# HoloCubicMCU_211230.net
KiCad netlist of a schematic drawn in Altium Designer
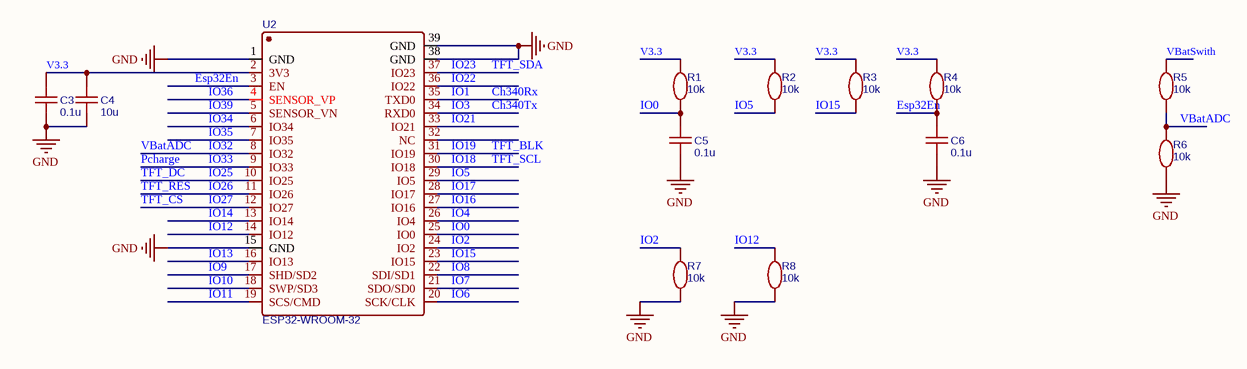
[diagram p0: HoloCubicMCU_211230.SchDoc]

(export (version "E")
  (design (tool "Eeschema 10.0.6"))
  (components
    (comp (ref "C3")
      (value "0.1u")
      (footprint "C0603")
      (fields (field (name "CONTRIBUTOR") "LCEDA_Lib"))
      (libsource (lib "altium-import") (part "root_1_0.1u_"))
    )
    (comp (ref "C4")
      (value "10u")
      (footprint "C0603")
      (fields (field (name "CONTRIBUTOR") "LCEDA_Lib"))
      (libsource (lib "altium-import") (part "root_1_0.1u_"))
    )
    (comp (ref "C5")
      (value "0.1u")
      (footprint "C0603")
      (fields (field (name "CONTRIBUTOR") "LCEDA_Lib"))
      (libsource (lib "altium-import") (part "root_1_0.1u_"))
    )
    (comp (ref "C6")
      (value "0.1u")
      (footprint "C0603")
      (fields (field (name "CONTRIBUTOR") "LCEDA_Lib"))
      (libsource (lib "altium-import") (part "root_1_0.1u_"))
    )
    (comp (ref "R1")
      (value "10k")
      (footprint "R0603")
      (fields (field (name "CONTRIBUTOR") "LCEDA_Lib"))
      (libsource (lib "altium-import") (part "root_1_10k_"))
    )
    (comp (ref "R2")
      (value "10k")
      (footprint "R0603")
      (fields (field (name "CONTRIBUTOR") "LCEDA_Lib"))
      (libsource (lib "altium-import") (part "root_1_10k_"))
    )
    (comp (ref "R3")
      (value "10k")
      (footprint "R0603")
      (fields (field (name "CONTRIBUTOR") "LCEDA_Lib"))
      (libsource (lib "altium-import") (part "root_1_10k_"))
    )
    (comp (ref "R4")
      (value "10k")
      (footprint "R0603")
      (fields (field (name "CONTRIBUTOR") "LCEDA_Lib"))
      (libsource (lib "altium-import") (part "root_1_10k_"))
    )
    (comp (ref "R5")
      (value "10k")
      (footprint "R0603")
      (fields (field (name "CONTRIBUTOR") "LCEDA_Lib"))
      (libsource (lib "altium-import") (part "root_1_10k_"))
    )
    (comp (ref "R6")
      (value "10k")
      (footprint "R0603")
      (fields (field (name "CONTRIBUTOR") "LCEDA_Lib"))
      (libsource (lib "altium-import") (part "root_1_10k_"))
    )
    (comp (ref "R7")
      (value "10k")
      (footprint "R0603")
      (fields (field (name "CONTRIBUTOR") "LCEDA_Lib"))
      (libsource (lib "altium-import") (part "root_1_10k_"))
    )
    (comp (ref "R8")
      (value "10k")
      (footprint "R0603")
      (fields (field (name "CONTRIBUTOR") "LCEDA_Lib"))
      (libsource (lib "altium-import") (part "root_1_10k_"))
    )
    (comp (ref "U2")
      (value "ESP32-WROOM-32")
      (footprint "WIFIM-SMD_ESP-32S")
      (fields (field (name "BOM_SUPPLIER PART") "C82899") (field (name "CONTRIBUTOR") "LCSC"))
      (libsource (lib "ZtYADLib") (part "ESP32-WROOM-32"))
    )
  )
  (nets
    (net (code "1") (name "/Ch340Rx") (class "Default")
      (node (ref "U2") (pin "35") (pinfunction "TXD0_35") (pintype "passive"))
    )
    (net (code "2") (name "/Ch340Tx") (class "Default")
      (node (ref "U2") (pin "34") (pinfunction "RXD0_34") (pintype "passive"))
    )
    (net (code "3") (name "/Esp32En") (class "Default")
      (node (ref "C6") (pin "2") (pinfunction "2_2") (pintype "passive"))
      (node (ref "R4") (pin "1") (pinfunction "1_1") (pintype "passive"))
      (node (ref "U2") (pin "3") (pinfunction "EN_3") (pintype "passive"))
    )
    (net (code "4") (name "/IO0") (class "Default")
      (node (ref "C5") (pin "2") (pinfunction "2_2") (pintype "passive"))
      (node (ref "R1") (pin "1") (pinfunction "1_1") (pintype "passive"))
      (node (ref "U2") (pin "25") (pinfunction "IO0_25") (pintype "passive"))
    )
    (net (code "5") (name "/IO2") (class "Default")
      (node (ref "R7") (pin "2") (pinfunction "2_2") (pintype "passive"))
      (node (ref "U2") (pin "24") (pinfunction "IO2_24") (pintype "passive"))
    )
    (net (code "6") (name "/IO4") (class "Default")
      (node (ref "U2") (pin "26") (pinfunction "IO4_26") (pintype "passive"))
    )
    (net (code "7") (name "/IO5") (class "Default")
      (node (ref "R2") (pin "1") (pinfunction "1_1") (pintype "passive"))
      (node (ref "U2") (pin "29") (pinfunction "IO5_29") (pintype "passive"))
    )
    (net (code "8") (name "/IO6") (class "Default")
      (node (ref "U2") (pin "20") (pinfunction "SCK/CLK_20") (pintype "passive"))
    )
    (net (code "9") (name "/IO7") (class "Default")
      (node (ref "U2") (pin "21") (pinfunction "SDO/SD0_21") (pintype "passive"))
    )
    (net (code "10") (name "/IO8") (class "Default")
      (node (ref "U2") (pin "22") (pinfunction "SDI/SD1_22") (pintype "passive"))
    )
    (net (code "11") (name "/IO9") (class "Default")
      (node (ref "U2") (pin "17") (pinfunction "SHD/SD2_17") (pintype "passive"))
    )
    (net (code "12") (name "/IO10") (class "Default")
      (node (ref "U2") (pin "18") (pinfunction "SWP/SD3_18") (pintype "passive"))
    )
    (net (code "13") (name "/IO11") (class "Default")
      (node (ref "U2") (pin "19") (pinfunction "SCS/CMD_19") (pintype "passive"))
    )
    (net (code "14") (name "/IO12") (class "Default")
      (node (ref "R8") (pin "2") (pinfunction "2_2") (pintype "passive"))
      (node (ref "U2") (pin "14") (pinfunction "IO12_14") (pintype "passive"))
    )
    (net (code "15") (name "/IO13") (class "Default")
      (node (ref "U2") (pin "16") (pinfunction "IO13_16") (pintype "passive"))
    )
    (net (code "16") (name "/IO14") (class "Default")
      (node (ref "U2") (pin "13") (pinfunction "IO14_13") (pintype "passive"))
    )
    (net (code "17") (name "/IO15") (class "Default")
      (node (ref "R3") (pin "1") (pinfunction "1_1") (pintype "passive"))
      (node (ref "U2") (pin "23") (pinfunction "IO15_23") (pintype "passive"))
    )
    (net (code "18") (name "/IO16") (class "Default")
      (node (ref "U2") (pin "27") (pinfunction "IO16_27") (pintype "passive"))
    )
    (net (code "19") (name "/IO17") (class "Default")
      (node (ref "U2") (pin "28") (pinfunction "IO17_28") (pintype "passive"))
    )
    (net (code "20") (name "/IO18") (class "Default")
      (node (ref "U2") (pin "30") (pinfunction "IO18_30") (pintype "passive"))
    )
    (net (code "21") (name "/IO19") (class "Default")
      (node (ref "U2") (pin "31") (pinfunction "IO19_31") (pintype "passive"))
    )
    (net (code "22") (name "/IO21") (class "Default")
      (node (ref "U2") (pin "33") (pinfunction "IO21_33") (pintype "passive"))
    )
    (net (code "23") (name "/IO22") (class "Default")
      (node (ref "U2") (pin "36") (pinfunction "IO22_36") (pintype "passive"))
    )
    (net (code "24") (name "/IO23") (class "Default")
      (node (ref "U2") (pin "37") (pinfunction "IO23_37") (pintype "passive"))
    )
    (net (code "25") (name "/IO25") (class "Default")
      (node (ref "U2") (pin "10") (pinfunction "IO25_10") (pintype "passive"))
    )
    (net (code "26") (name "/IO26") (class "Default")
      (node (ref "U2") (pin "11") (pinfunction "IO26_11") (pintype "passive"))
    )
    (net (code "27") (name "/IO27") (class "Default")
      (node (ref "U2") (pin "12") (pinfunction "IO27_12") (pintype "passive"))
    )
    (net (code "28") (name "/IO32") (class "Default")
      (node (ref "R5") (pin "1") (pinfunction "1_1") (pintype "passive"))
      (node (ref "R6") (pin "2") (pinfunction "2_2") (pintype "passive"))
      (node (ref "U2") (pin "8") (pinfunction "IO32_8") (pintype "passive"))
    )
    (net (code "29") (name "/IO33") (class "Default")
      (node (ref "U2") (pin "9") (pinfunction "IO33_9") (pintype "passive"))
    )
    (net (code "30") (name "/IO34") (class "Default")
      (node (ref "U2") (pin "6") (pinfunction "IO34_6") (pintype "passive"))
    )
    (net (code "31") (name "/IO35") (class "Default")
      (node (ref "U2") (pin "7") (pinfunction "IO35_7") (pintype "passive"))
    )
    (net (code "32") (name "/IO36") (class "Default")
      (node (ref "U2") (pin "4") (pinfunction "SENSOR_VP_4") (pintype "passive"))
    )
    (net (code "33") (name "/IO39") (class "Default")
      (node (ref "U2") (pin "5") (pinfunction "SENSOR_VN_5") (pintype "passive"))
    )
    (net (code "34") (name "/V3.3") (class "Default")
      (node (ref "C3") (pin "2") (pinfunction "2_2") (pintype "passive"))
      (node (ref "C4") (pin "2") (pinfunction "2_2") (pintype "passive"))
      (node (ref "R1") (pin "2") (pinfunction "2_2") (pintype "passive"))
      (node (ref "R2") (pin "2") (pinfunction "2_2") (pintype "passive"))
      (node (ref "R3") (pin "2") (pinfunction "2_2") (pintype "passive"))
      (node (ref "R4") (pin "2") (pinfunction "2_2") (pintype "passive"))
      (node (ref "U2") (pin "2") (pinfunction "3V3_2") (pintype "passive"))
    )
    (net (code "35") (name "/VBatSwith") (class "Default")
      (node (ref "R5") (pin "2") (pinfunction "2_2") (pintype "passive"))
    )
    (net (code "36") (name "GND") (class "Default")
      (node (ref "C3") (pin "1") (pinfunction "1_1") (pintype "passive"))
      (node (ref "C4") (pin "1") (pinfunction "1_1") (pintype "passive"))
      (node (ref "C5") (pin "1") (pinfunction "1_1") (pintype "passive"))
      (node (ref "C6") (pin "1") (pinfunction "1_1") (pintype "passive"))
      (node (ref "R6") (pin "1") (pinfunction "1_1") (pintype "passive"))
      (node (ref "R7") (pin "1") (pinfunction "1_1") (pintype "passive"))
      (node (ref "R8") (pin "1") (pinfunction "1_1") (pintype "passive"))
      (node (ref "U2") (pin "1") (pinfunction "GND_1") (pintype "passive"))
      (node (ref "U2") (pin "15") (pinfunction "GND_15") (pintype "passive"))
      (node (ref "U2") (pin "38") (pinfunction "GND_38") (pintype "passive"))
      (node (ref "U2") (pin "39") (pinfunction "GND_39") (pintype "passive"))
    )
    (net (code "37") (name "unconnected-(U2-NC-Pad32)") (class "Default")
      (node (ref "U2") (pin "32") (pinfunction "NC_32") (pintype "passive"))
    )
  )
)
